# D5S.net
KiCad netlist of a schematic drawn in EAGLE
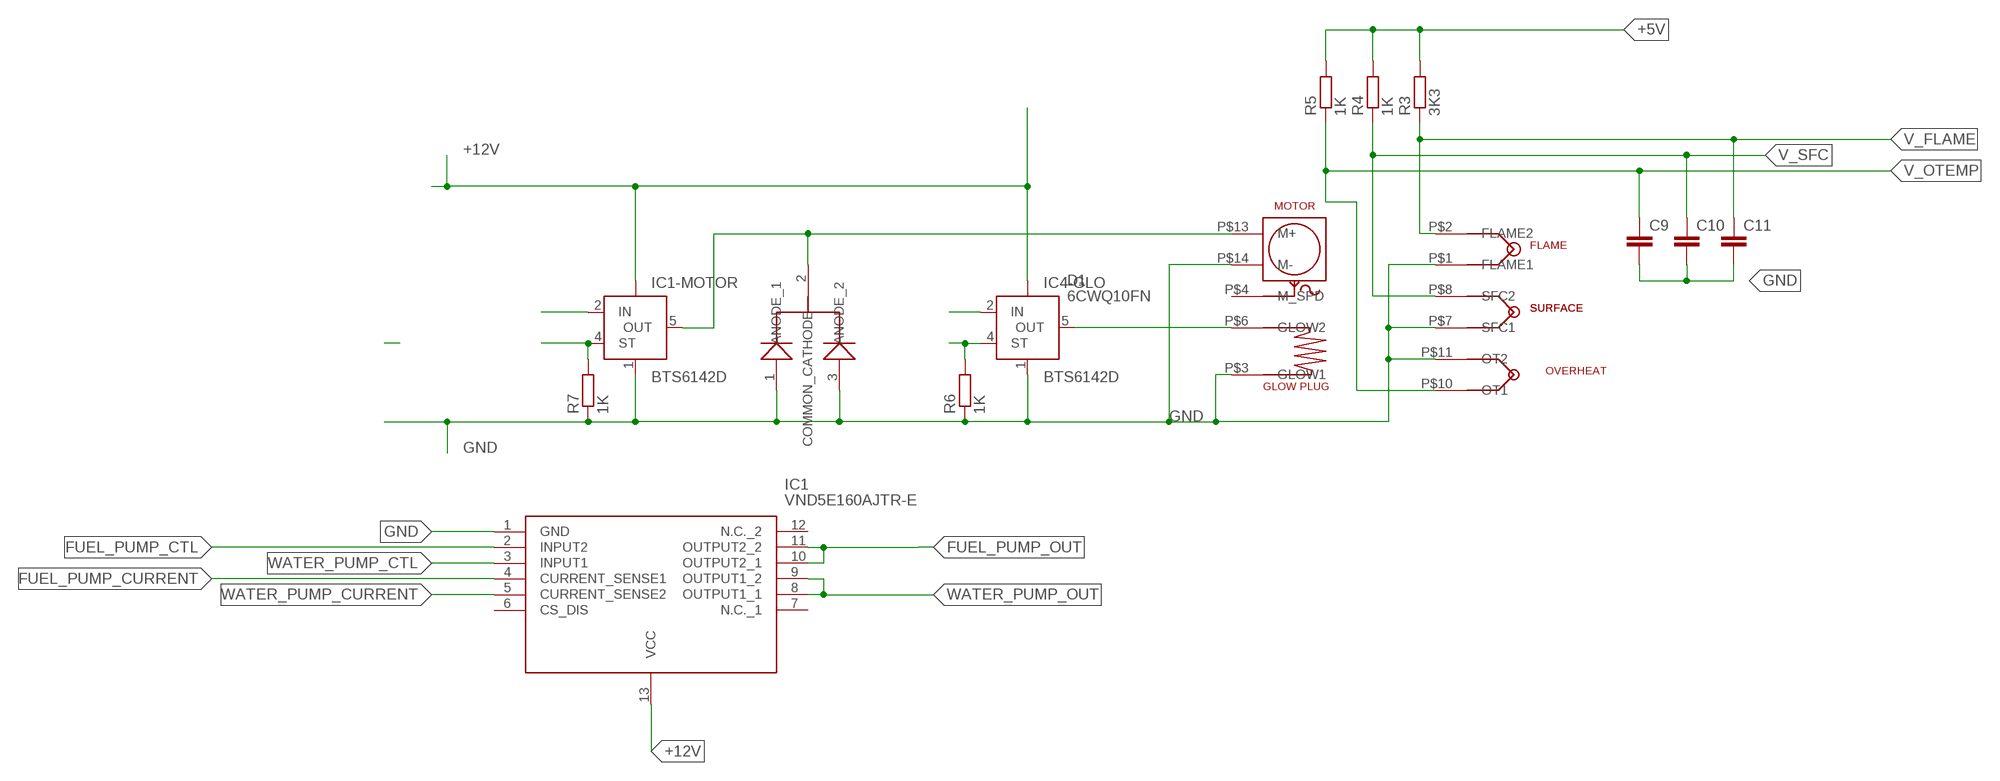
[diagram p0: schematic, sheet 1]
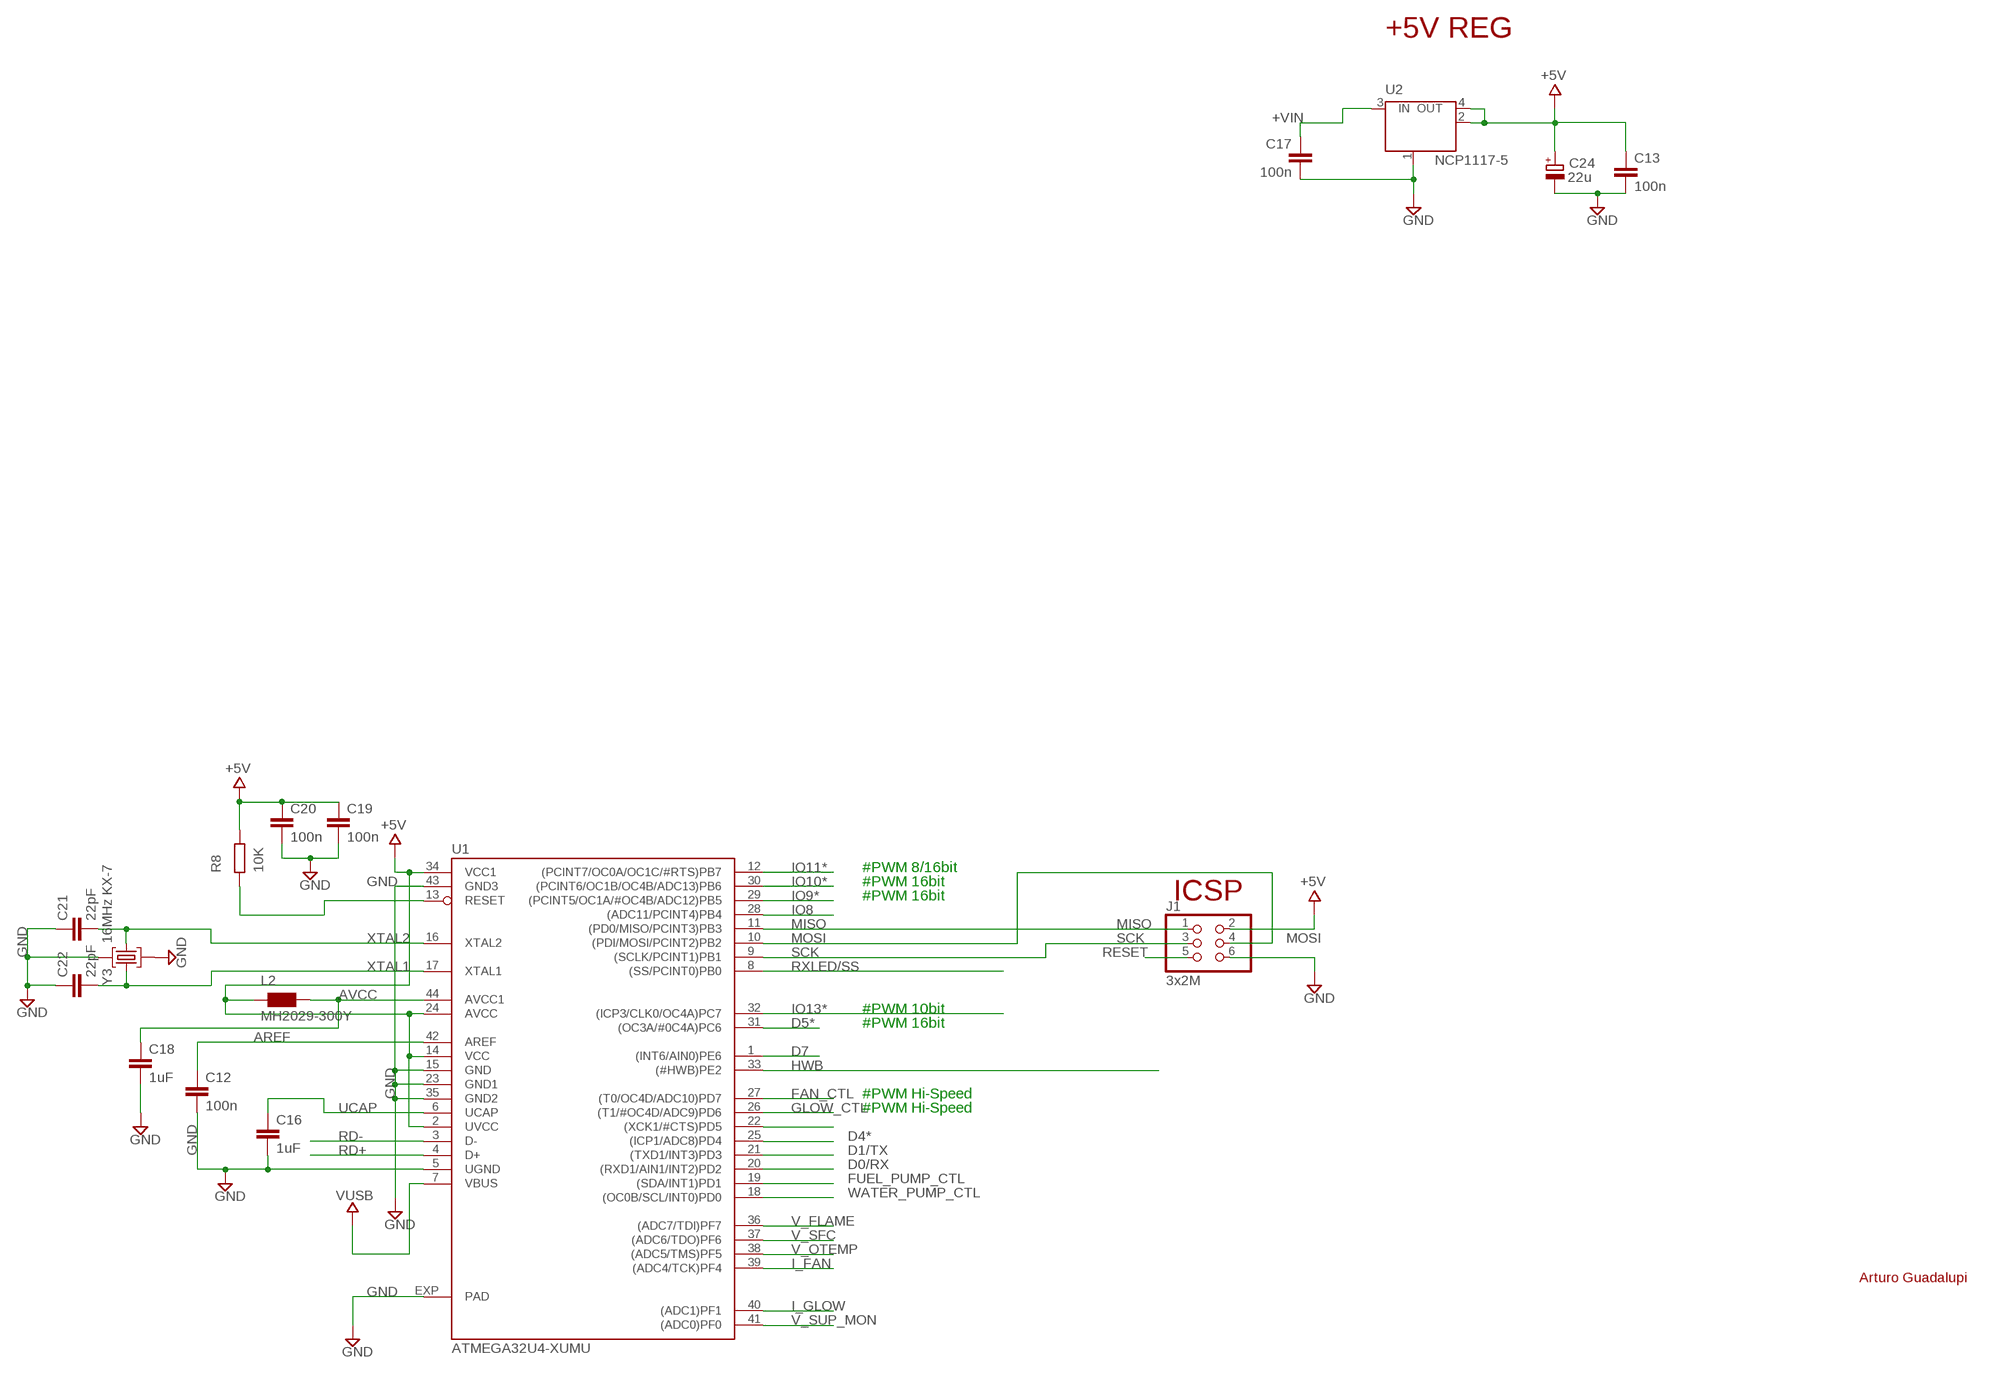
[diagram p1: schematic, sheet 2]

(export (version "E")
  (design (tool "Eeschema 10.0.6"))
  (components
    (comp (ref "C9")
      (value "C-EUC0603")
      (footprint "eagle-import:C0603")
      (libsource (lib "eagle-import") (part "resistor_C-EUC0603"))
    )
    (comp (ref "C10")
      (value "C-EUC0603")
      (footprint "eagle-import:C0603")
      (libsource (lib "eagle-import") (part "resistor_C-EUC0603"))
    )
    (comp (ref "C11")
      (value "C-EUC0603")
      (footprint "eagle-import:C0603")
      (libsource (lib "eagle-import") (part "resistor_C-EUC0603"))
    )
    (comp (ref "D1")
      (value "6CWQ10FN")
      (footprint "eagle-import:6CWQ10FN")
      (fields (field (name "MOUSER_PART_NUMBER") "844-6CWQ10FN"))
      (libsource (lib "eagle-import") (part "6CWQ10FN"))
    )
    (comp (ref "IC1")
      (value "VND5E160AJTR-E")
      (footprint "eagle-import:SOP80P600X162-13N")
      (fields (field (name "MOUSER_PART_NUMBER") "511-VND5E160AJTR-E"))
      (libsource (lib "eagle-import") (part "VND5E160AJTR-E"))
    )
    (comp (ref "IC1-MOTOR")
      (value "BTS6142D")
      (footprint "eagle-import:TO252-5-11")
      (libsource (lib "eagle-import") (part "BTS428L2"))
    )
    (comp (ref "IC4-GLO")
      (value "BTS6142D")
      (footprint "eagle-import:TO252-5-11")
      (libsource (lib "eagle-import") (part "BTS428L2"))
    )
    (comp (ref "R3")
      (value "3K3")
      (footprint "eagle-import:R0603")
      (libsource (lib "eagle-import") (part "resistor_R-EU_R0603"))
    )
    (comp (ref "R4")
      (value "1K")
      (footprint "eagle-import:R0603")
      (libsource (lib "eagle-import") (part "resistor_R-EU_R0603"))
    )
    (comp (ref "R5")
      (value "1K")
      (footprint "eagle-import:R0603")
      (libsource (lib "eagle-import") (part "resistor_R-EU_R0603"))
    )
    (comp (ref "R6")
      (value "1K")
      (footprint "eagle-import:R0603")
      (libsource (lib "eagle-import") (part "resistor_R-EU_R0603"))
    )
    (comp (ref "R7")
      (value "1K")
      (footprint "eagle-import:R0603")
      (libsource (lib "eagle-import") (part "resistor_R-EU_R0603"))
    )
    (comp (ref "U$1")
      (value "D5S")
      (footprint "eagle-import:PCB")
      (libsource (lib "eagle-import") (part "D5S"))
    )
    (comp (ref "C12")
      (value "100n")
      (footprint "eagle-import:C0402")
      (libsource (lib "eagle-import") (part "C-EUC0402"))
    )
    (comp (ref "C13")
      (value "100n")
      (footprint "eagle-import:C0402")
      (libsource (lib "eagle-import") (part "C-EUC0402"))
    )
    (comp (ref "C16")
      (value "1uF")
      (footprint "eagle-import:C0402")
      (libsource (lib "eagle-import") (part "C-EUC0402"))
    )
    (comp (ref "C17")
      (value "100n")
      (footprint "eagle-import:C0402")
      (libsource (lib "eagle-import") (part "C-EUC0402"))
    )
    (comp (ref "C18")
      (value "1uF")
      (footprint "eagle-import:C0402")
      (libsource (lib "eagle-import") (part "C-EUC0402"))
    )
    (comp (ref "C19")
      (value "100n")
      (footprint "eagle-import:C0402")
      (libsource (lib "eagle-import") (part "C-EUC0402"))
    )
    (comp (ref "C20")
      (value "100n")
      (footprint "eagle-import:C0402")
      (libsource (lib "eagle-import") (part "C-EUC0402"))
    )
    (comp (ref "C21")
      (value "22pF")
      (footprint "eagle-import:C0402")
      (libsource (lib "eagle-import") (part "C-EUC0402"))
    )
    (comp (ref "C22")
      (value "22pF")
      (footprint "eagle-import:C0402")
      (libsource (lib "eagle-import") (part "C-EUC0402"))
    )
    (comp (ref "C24")
      (value "22u")
      (footprint "eagle-import:SMC_B")
      (libsource (lib "eagle-import") (part "CPOL-EUSMCB"))
    )
    (comp (ref "J1")
      (value "3x2M")
      (footprint "eagle-import:2X03")
      (libsource (lib "eagle-import") (part "PINHD-2X3"))
    )
    (comp (ref "L2")
      (value "MH2029-300Y")
      (footprint "eagle-import:0805")
      (libsource (lib "eagle-import") (part "WE-CBF_0805"))
    )
    (comp (ref "R8")
      (value "10K")
      (footprint "eagle-import:R0402")
      (libsource (lib "eagle-import") (part "R-EU_R0402"))
    )
    (comp (ref "U1")
      (value "ATMEGA32U4-XUMU")
      (footprint "eagle-import:QFN44ML7X7")
      (libsource (lib "eagle-import") (part "ATMEGA32U4-XUMU"))
    )
    (comp (ref "U2")
      (value "NCP1117-5")
      (footprint "eagle-import:SOT223")
      (libsource (lib "eagle-import") (part "LINEAR_MC33269ST"))
    )
    (comp (ref "Y3")
      (value "16MHz KX-7")
      (footprint "eagle-import:CRYSTAL-3.2-2.5")
      (libsource (lib "eagle-import") (part "CRYSTAL-3.2-2.5"))
    )
  )
  (nets
    (net (code "1") (name "+5V") (class "Default")
      (node (ref "C13") (pin "1") (pinfunction "1_1") (pintype "passive"))
      (node (ref "C19") (pin "1") (pinfunction "1_1") (pintype "passive"))
      (node (ref "C20") (pin "1") (pinfunction "1_1") (pintype "passive"))
      (node (ref "C24") (pin "+") (pinfunction "+_+") (pintype "passive"))
      (node (ref "J1") (pin "2") (pinfunction "2_2") (pintype "passive"))
      (node (ref "L2") (pin "1") (pinfunction "1_1") (pintype "passive"))
      (node (ref "R3") (pin "2") (pinfunction "2_2") (pintype "passive"))
      (node (ref "R4") (pin "2") (pinfunction "2_2") (pintype "passive"))
      (node (ref "R5") (pin "2") (pinfunction "2_2") (pintype "passive"))
      (node (ref "R8") (pin "1") (pinfunction "1_1") (pintype "passive"))
      (node (ref "U1") (pin "14") (pinfunction "VCC_14") (pintype "power_in"))
      (node (ref "U1") (pin "2") (pinfunction "UVCC_2") (pintype "power_in"))
      (node (ref "U1") (pin "24") (pinfunction "AVCC_24") (pintype "power_in"))
      (node (ref "U1") (pin "34") (pinfunction "VCC1_34") (pintype "power_in"))
      (node (ref "U2") (pin "2") (pinfunction "OUT_2") (pintype "passive"))
      (node (ref "U2") (pin "4") (pinfunction "OUT_4") (pintype "passive"))
    )
    (net (code "2") (name "+12V") (class "Default")
      (node (ref "IC1") (pin "13") (pinfunction "VCC_13") (pintype "bidirectional"))
      (node (ref "IC1-MOTOR") (pin "TAB") (pinfunction "VBB_TAB") (pintype "power_in"))
      (node (ref "IC4-GLO") (pin "TAB") (pinfunction "VBB_TAB") (pintype "power_in"))
    )
    (net (code "3") (name "+VIN") (class "Default")
      (node (ref "C17") (pin "1") (pinfunction "1_1") (pintype "passive"))
      (node (ref "U2") (pin "3") (pinfunction "IN_3") (pintype "input"))
    )
    (net (code "4") (name "AREF") (class "Default")
      (node (ref "C12") (pin "1") (pinfunction "1_1") (pintype "passive"))
      (node (ref "U1") (pin "42") (pinfunction "AREF_42") (pintype "power_in"))
    )
    (net (code "5") (name "AVCC") (class "Default")
      (node (ref "C18") (pin "1") (pinfunction "1_1") (pintype "passive"))
      (node (ref "L2") (pin "2") (pinfunction "2_2") (pintype "passive"))
      (node (ref "U1") (pin "44") (pinfunction "AVCC1_44") (pintype "power_in"))
    )
    (net (code "6") (name "D0{slash}RX") (class "Default")
      (node (ref "U1") (pin "20") (pinfunction "(RXD1/AIN1/INT2)PD2_20") (pintype "bidirectional"))
    )
    (net (code "7") (name "D1{slash}TX") (class "Default")
      (node (ref "U1") (pin "21") (pinfunction "(TXD1/INT3)PD3_21") (pintype "bidirectional"))
    )
    (net (code "8") (name "D4*") (class "Default")
      (node (ref "U1") (pin "25") (pinfunction "(ICP1/ADC8)PD4_25") (pintype "bidirectional"))
    )
    (net (code "9") (name "D5*") (class "Default")
      (node (ref "U1") (pin "31") (pinfunction "(OC3A/#0C4A)PC6_31") (pintype "bidirectional"))
    )
    (net (code "10") (name "D7") (class "Default")
      (node (ref "U1") (pin "1") (pinfunction "(INT6/AIN0)PE6_1") (pintype "bidirectional"))
    )
    (net (code "11") (name "FAN_CTL") (class "Default")
      (node (ref "IC1-MOTOR") (pin "2") (pinfunction "IN_2") (pintype "input"))
      (node (ref "U1") (pin "27") (pinfunction "(T0/OC4D/ADC10)PD7_27") (pintype "bidirectional"))
    )
    (net (code "12") (name "FUEL_PUMP_CTL") (class "Default")
      (node (ref "IC1") (pin "2") (pinfunction "INPUT2_2") (pintype "bidirectional"))
      (node (ref "U1") (pin "19") (pinfunction "(SDA/INT1)PD1_19") (pintype "bidirectional"))
    )
    (net (code "13") (name "FUEL_PUMP_CURRENT") (class "Default")
      (node (ref "IC1") (pin "4") (pinfunction "CURRENT_SENSE1_4") (pintype "bidirectional"))
    )
    (net (code "14") (name "FUEL_PUMP_OUT") (class "Default")
      (node (ref "IC1") (pin "10") (pinfunction "OUTPUT2_1_10") (pintype "bidirectional"))
      (node (ref "IC1") (pin "11") (pinfunction "OUTPUT2_2_11") (pintype "bidirectional"))
    )
    (net (code "15") (name "GLOW_CTL") (class "Default")
      (node (ref "IC4-GLO") (pin "2") (pinfunction "IN_2") (pintype "input"))
      (node (ref "U1") (pin "26") (pinfunction "(T1/#OC4D/ADC9)PD6_26") (pintype "bidirectional"))
    )
    (net (code "16") (name "GND") (class "Default")
      (node (ref "C10") (pin "2") (pinfunction "2_2") (pintype "passive"))
      (node (ref "C11") (pin "2") (pinfunction "2_2") (pintype "passive"))
      (node (ref "C12") (pin "2") (pinfunction "2_2") (pintype "passive"))
      (node (ref "C13") (pin "2") (pinfunction "2_2") (pintype "passive"))
      (node (ref "C16") (pin "2") (pinfunction "2_2") (pintype "passive"))
      (node (ref "C17") (pin "2") (pinfunction "2_2") (pintype "passive"))
      (node (ref "C18") (pin "2") (pinfunction "2_2") (pintype "passive"))
      (node (ref "C19") (pin "2") (pinfunction "2_2") (pintype "passive"))
      (node (ref "C20") (pin "2") (pinfunction "2_2") (pintype "passive"))
      (node (ref "C21") (pin "1") (pinfunction "1_1") (pintype "passive"))
      (node (ref "C22") (pin "1") (pinfunction "1_1") (pintype "passive"))
      (node (ref "C24") (pin "-") (pinfunction "-_-") (pintype "passive"))
      (node (ref "C9") (pin "2") (pinfunction "2_2") (pintype "passive"))
      (node (ref "D1") (pin "1") (pinfunction "ANODE_1_1") (pintype "bidirectional"))
      (node (ref "D1") (pin "3") (pinfunction "ANODE_2_3") (pintype "bidirectional"))
      (node (ref "IC1") (pin "1") (pinfunction "GND_1") (pintype "bidirectional"))
      (node (ref "IC1-MOTOR") (pin "1") (pinfunction "GND_1") (pintype "power_in"))
      (node (ref "IC4-GLO") (pin "1") (pinfunction "GND_1") (pintype "power_in"))
      (node (ref "J1") (pin "6") (pinfunction "6_6") (pintype "passive"))
      (node (ref "R6") (pin "1") (pinfunction "1_1") (pintype "passive"))
      (node (ref "R7") (pin "1") (pinfunction "1_1") (pintype "passive"))
      (node (ref "U$1") (pin "P$1") (pinfunction "FLAME1_P$1") (pintype "bidirectional"))
      (node (ref "U$1") (pin "P$11") (pinfunction "OT2_P$11") (pintype "bidirectional"))
      (node (ref "U$1") (pin "P$14") (pinfunction "M-_P$14") (pintype "bidirectional"))
      (node (ref "U$1") (pin "P$3") (pinfunction "GLOW1_P$3") (pintype "bidirectional"))
      (node (ref "U$1") (pin "P$7") (pinfunction "SFC1_P$7") (pintype "bidirectional"))
      (node (ref "U1") (pin "15") (pinfunction "GND_15") (pintype "power_in"))
      (node (ref "U1") (pin "23") (pinfunction "GND1_23") (pintype "power_in"))
      (node (ref "U1") (pin "35") (pinfunction "GND2_35") (pintype "power_in"))
      (node (ref "U1") (pin "43") (pinfunction "GND3_43") (pintype "power_in"))
      (node (ref "U1") (pin "5") (pinfunction "UGND_5") (pintype "power_in"))
      (node (ref "U1") (pin "EXP") (pinfunction "PAD_EXP") (pintype "power_in"))
      (node (ref "U2") (pin "1") (pinfunction "GND/ADJ_1") (pintype "input"))
      (node (ref "Y3") (pin "2") (pinfunction "GND_2") (pintype "passive"))
      (node (ref "Y3") (pin "4") (pinfunction "GND_4") (pintype "passive"))
    )
    (net (code "17") (name "HWB") (class "Default")
      (node (ref "U1") (pin "33") (pinfunction "(#HWB)PE2_33") (pintype "bidirectional"))
    )
    (net (code "18") (name "IO8") (class "Default")
      (node (ref "U1") (pin "28") (pinfunction "(ADC11/PCINT4)PB4_28") (pintype "bidirectional"))
    )
    (net (code "19") (name "IO9*") (class "Default")
      (node (ref "U1") (pin "29") (pinfunction "(PCINT5/OC1A/#OC4B/ADC12)PB5_29") (pintype "bidirectional"))
    )
    (net (code "20") (name "IO10*") (class "Default")
      (node (ref "U1") (pin "30") (pinfunction "(PCINT6/OC1B/OC4B/ADC13)PB6_30") (pintype "bidirectional"))
    )
    (net (code "21") (name "IO11*") (class "Default")
      (node (ref "U1") (pin "12") (pinfunction "(PCINT7/OC0A/OC1C/#RTS)PB7_12") (pintype "bidirectional"))
    )
    (net (code "22") (name "IO13*") (class "Default")
      (node (ref "U1") (pin "32") (pinfunction "(ICP3/CLK0/OC4A)PC7_32") (pintype "bidirectional"))
    )
    (net (code "23") (name "I_FAN") (class "Default")
      (node (ref "U1") (pin "39") (pinfunction "(ADC4/TCK)PF4_39") (pintype "bidirectional"))
    )
    (net (code "24") (name "I_GLOW") (class "Default")
      (node (ref "U1") (pin "40") (pinfunction "(ADC1)PF1_40") (pintype "bidirectional"))
    )
    (net (code "25") (name "MISO") (class "Default")
      (node (ref "J1") (pin "1") (pinfunction "1_1") (pintype "passive"))
      (node (ref "U1") (pin "11") (pinfunction "(PD0/MISO/PCINT3)PB3_11") (pintype "bidirectional"))
    )
    (net (code "26") (name "MOSI") (class "Default")
      (node (ref "J1") (pin "4") (pinfunction "4_4") (pintype "passive"))
      (node (ref "U1") (pin "10") (pinfunction "(PDI/MOSI/PCINT2)PB2_10") (pintype "bidirectional"))
    )
    (net (code "27") (name "Net-(D1-COMMON_CATHODE)") (class "Default")
      (node (ref "D1") (pin "2") (pinfunction "COMMON_CATHODE_2") (pintype "bidirectional"))
      (node (ref "IC1-MOTOR") (pin "5") (pinfunction "OUT_5") (pintype "output"))
      (node (ref "U$1") (pin "P$13") (pinfunction "M+_P$13") (pintype "bidirectional"))
    )
    (net (code "28") (name "Net-(IC1-MOTOR-ST)") (class "Default")
      (node (ref "IC1-MOTOR") (pin "4") (pinfunction "ST_4") (pintype "input"))
      (node (ref "R7") (pin "2") (pinfunction "2_2") (pintype "passive"))
    )
    (net (code "29") (name "Net-(IC4-GLO-OUT)") (class "Default")
      (node (ref "IC4-GLO") (pin "5") (pinfunction "OUT_5") (pintype "output"))
      (node (ref "U$1") (pin "P$6") (pinfunction "GLOW2_P$6") (pintype "bidirectional"))
    )
    (net (code "30") (name "Net-(IC4-GLO-ST)") (class "Default")
      (node (ref "IC4-GLO") (pin "4") (pinfunction "ST_4") (pintype "input"))
      (node (ref "R6") (pin "2") (pinfunction "2_2") (pintype "passive"))
    )
    (net (code "31") (name "RD+") (class "Default")
      (node (ref "U1") (pin "4") (pinfunction "D+_4") (pintype "bidirectional"))
    )
    (net (code "32") (name "RD-") (class "Default")
      (node (ref "U1") (pin "3") (pinfunction "D-_3") (pintype "bidirectional"))
    )
    (net (code "33") (name "RESET") (class "Default")
      (node (ref "J1") (pin "5") (pinfunction "5_5") (pintype "passive"))
      (node (ref "R8") (pin "2") (pinfunction "2_2") (pintype "passive"))
      (node (ref "U1") (pin "13") (pinfunction "RESET_13") (pintype "input"))
    )
    (net (code "34") (name "RXLED{slash}SS") (class "Default")
      (node (ref "U1") (pin "8") (pinfunction "(SS/PCINT0)PB0_8") (pintype "bidirectional"))
    )
    (net (code "35") (name "SCK") (class "Default")
      (node (ref "J1") (pin "3") (pinfunction "3_3") (pintype "passive"))
      (node (ref "U1") (pin "9") (pinfunction "(SCLK/PCINT1)PB1_9") (pintype "bidirectional"))
    )
    (net (code "36") (name "UCAP") (class "Default")
      (node (ref "C16") (pin "1") (pinfunction "1_1") (pintype "passive"))
      (node (ref "U1") (pin "6") (pinfunction "UCAP_6") (pintype "passive"))
    )
    (net (code "37") (name "VUSB") (class "Default")
      (node (ref "U1") (pin "7") (pinfunction "VBUS_7") (pintype "input"))
    )
    (net (code "38") (name "V_FLAME") (class "Default")
      (node (ref "C11") (pin "1") (pinfunction "1_1") (pintype "passive"))
      (node (ref "R3") (pin "1") (pinfunction "1_1") (pintype "passive"))
      (node (ref "U$1") (pin "P$2") (pinfunction "FLAME2_P$2") (pintype "bidirectional"))
      (node (ref "U1") (pin "36") (pinfunction "(ADC7/TDI)PF7_36") (pintype "bidirectional"))
    )
    (net (code "39") (name "V_OTEMP") (class "Default")
      (node (ref "C9") (pin "1") (pinfunction "1_1") (pintype "passive"))
      (node (ref "R5") (pin "1") (pinfunction "1_1") (pintype "passive"))
      (node (ref "U$1") (pin "P$10") (pinfunction "OT1_P$10") (pintype "bidirectional"))
      (node (ref "U1") (pin "38") (pinfunction "(ADC5/TMS)PF5_38") (pintype "bidirectional"))
    )
    (net (code "40") (name "V_SFC") (class "Default")
      (node (ref "C10") (pin "1") (pinfunction "1_1") (pintype "passive"))
      (node (ref "R4") (pin "1") (pinfunction "1_1") (pintype "passive"))
      (node (ref "U$1") (pin "P$8") (pinfunction "SFC2_P$8") (pintype "bidirectional"))
      (node (ref "U1") (pin "37") (pinfunction "(ADC6/TDO)PF6_37") (pintype "bidirectional"))
    )
    (net (code "41") (name "V_SUP_MON") (class "Default")
      (node (ref "U1") (pin "41") (pinfunction "(ADC0)PF0_41") (pintype "bidirectional"))
    )
    (net (code "42") (name "WATER_PUMP_CTL") (class "Default")
      (node (ref "IC1") (pin "3") (pinfunction "INPUT1_3") (pintype "bidirectional"))
      (node (ref "U1") (pin "18") (pinfunction "(OC0B/SCL/INT0)PD0_18") (pintype "bidirectional"))
    )
    (net (code "43") (name "WATER_PUMP_CURRENT") (class "Default")
      (node (ref "IC1") (pin "5") (pinfunction "CURRENT_SENSE2_5") (pintype "bidirectional"))
    )
    (net (code "44") (name "WATER_PUMP_OUT") (class "Default")
      (node (ref "IC1") (pin "8") (pinfunction "OUTPUT1_1_8") (pintype "bidirectional"))
      (node (ref "IC1") (pin "9") (pinfunction "OUTPUT1_2_9") (pintype "bidirectional"))
    )
    (net (code "45") (name "XTAL1") (class "Default")
      (node (ref "C22") (pin "2") (pinfunction "2_2") (pintype "passive"))
      (node (ref "U1") (pin "17") (pinfunction "XTAL1_17") (pintype "bidirectional"))
      (node (ref "Y3") (pin "3") (pinfunction "C2_3") (pintype "passive"))
    )
    (net (code "46") (name "XTAL2") (class "Default")
      (node (ref "C21") (pin "2") (pinfunction "2_2") (pintype "passive"))
      (node (ref "U1") (pin "16") (pinfunction "XTAL2_16") (pintype "bidirectional"))
      (node (ref "Y3") (pin "1") (pinfunction "C1_1") (pintype "passive"))
    )
    (net (code "47") (name "unconnected-(IC1-CS_DIS-Pad6)") (class "Default")
      (node (ref "IC1") (pin "6") (pinfunction "CS_DIS_6") (pintype "bidirectional"))
    )
    (net (code "48") (name "unconnected-(IC1-N.C._1-Pad7)") (class "Default")
      (node (ref "IC1") (pin "7") (pinfunction "N.C._1_7") (pintype "bidirectional"))
    )
    (net (code "49") (name "unconnected-(IC1-N.C._2-Pad12)") (class "Default")
      (node (ref "IC1") (pin "12") (pinfunction "N.C._2_12") (pintype "bidirectional"))
    )
    (net (code "50") (name "unconnected-(U$1-M_SPD-PadP$4)") (class "Default")
      (node (ref "U$1") (pin "P$4") (pinfunction "M_SPD_P$4") (pintype "bidirectional"))
    )
    (net (code "51") (name "unconnected-(U1-(XCK1{slash}#CTS)PD5-Pad22)") (class "Default")
      (node (ref "U1") (pin "22") (pinfunction "(XCK1/#CTS)PD5_22") (pintype "bidirectional"))
    )
  )
)
